# EEPROM_SMD_Breakout_Jumper.net
KiCad netlist of a schematic drawn in EAGLE
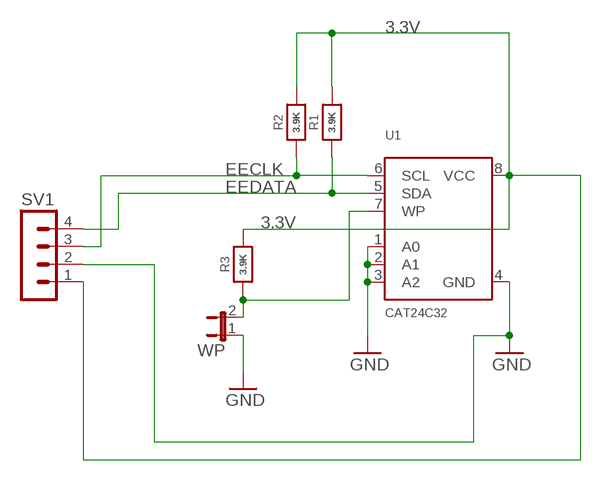
[diagram p0: schematic, sheet 1]

(export (version "E")
  (design (tool "Eeschema 10.0.6"))
  (components
    (comp (ref "R1")
      (value "3.9K")
      (footprint "eagle-import:0805-NO")
      (libsource (lib "eagle-import") (part "RESISTOR0805_NOOUTLINE"))
    )
    (comp (ref "R2")
      (value "3.9K")
      (footprint "eagle-import:0805-NO")
      (libsource (lib "eagle-import") (part "RESISTOR0805_NOOUTLINE"))
    )
    (comp (ref "R3")
      (value "3.9K")
      (footprint "eagle-import:0805-NO")
      (libsource (lib "eagle-import") (part "RESISTOR0805_NOOUTLINE"))
    )
    (comp (ref "SV1")
      (value "MA04-1")
      (footprint "eagle-import:MA04-1")
      (libsource (lib "eagle-import") (part "MA04-1"))
    )
    (comp (ref "U1")
      (value "CAT24C32")
      (footprint "eagle-import:SOIC8_150MIL")
      (libsource (lib "eagle-import") (part "EEPROM_I2C_SOIC8_GENERIC"))
    )
    (comp (ref "WP")
      (value "JP1E")
      (footprint "eagle-import:JP1")
      (libsource (lib "eagle-import") (part "JP1E"))
    )
  )
  (nets
    (net (code "1") (name "/3.3V") (class "Default")
      (node (ref "R1") (pin "2") (pinfunction "2_2") (pintype "passive"))
      (node (ref "R2") (pin "2") (pinfunction "2_2") (pintype "passive"))
      (node (ref "R3") (pin "2") (pinfunction "2_2") (pintype "passive"))
      (node (ref "SV1") (pin "1") (pinfunction "1_1") (pintype "passive"))
      (node (ref "U1") (pin "8") (pinfunction "VCC_8") (pintype "power_in"))
    )
    (net (code "2") (name "/EECLK") (class "Default")
      (node (ref "R2") (pin "1") (pinfunction "1_1") (pintype "passive"))
      (node (ref "SV1") (pin "3") (pinfunction "3_3") (pintype "passive"))
      (node (ref "U1") (pin "6") (pinfunction "SCL_6") (pintype "input"))
    )
    (net (code "3") (name "/EEDATA") (class "Default")
      (node (ref "R1") (pin "1") (pinfunction "1_1") (pintype "passive"))
      (node (ref "SV1") (pin "4") (pinfunction "4_4") (pintype "passive"))
      (node (ref "U1") (pin "5") (pinfunction "SDA_5") (pintype "bidirectional"))
    )
    (net (code "4") (name "GND") (class "Default")
      (node (ref "SV1") (pin "2") (pinfunction "2_2") (pintype "passive"))
      (node (ref "U1") (pin "1") (pinfunction "A0_1") (pintype "input"))
      (node (ref "U1") (pin "2") (pinfunction "A1_2") (pintype "input"))
      (node (ref "U1") (pin "3") (pinfunction "A2_3") (pintype "input"))
      (node (ref "U1") (pin "4") (pinfunction "GND_4") (pintype "power_in"))
      (node (ref "WP") (pin "1") (pinfunction "1_1") (pintype "passive"))
    )
    (net (code "5") (name "Net-(U1-WP)") (class "Default")
      (node (ref "R3") (pin "1") (pinfunction "1_1") (pintype "passive"))
      (node (ref "U1") (pin "7") (pinfunction "WP_7") (pintype "input"))
      (node (ref "WP") (pin "2") (pinfunction "2_2") (pintype "passive"))
    )
  )
)
